# bombclock_1_2.net
KiCad netlist of a schematic drawn in EAGLE
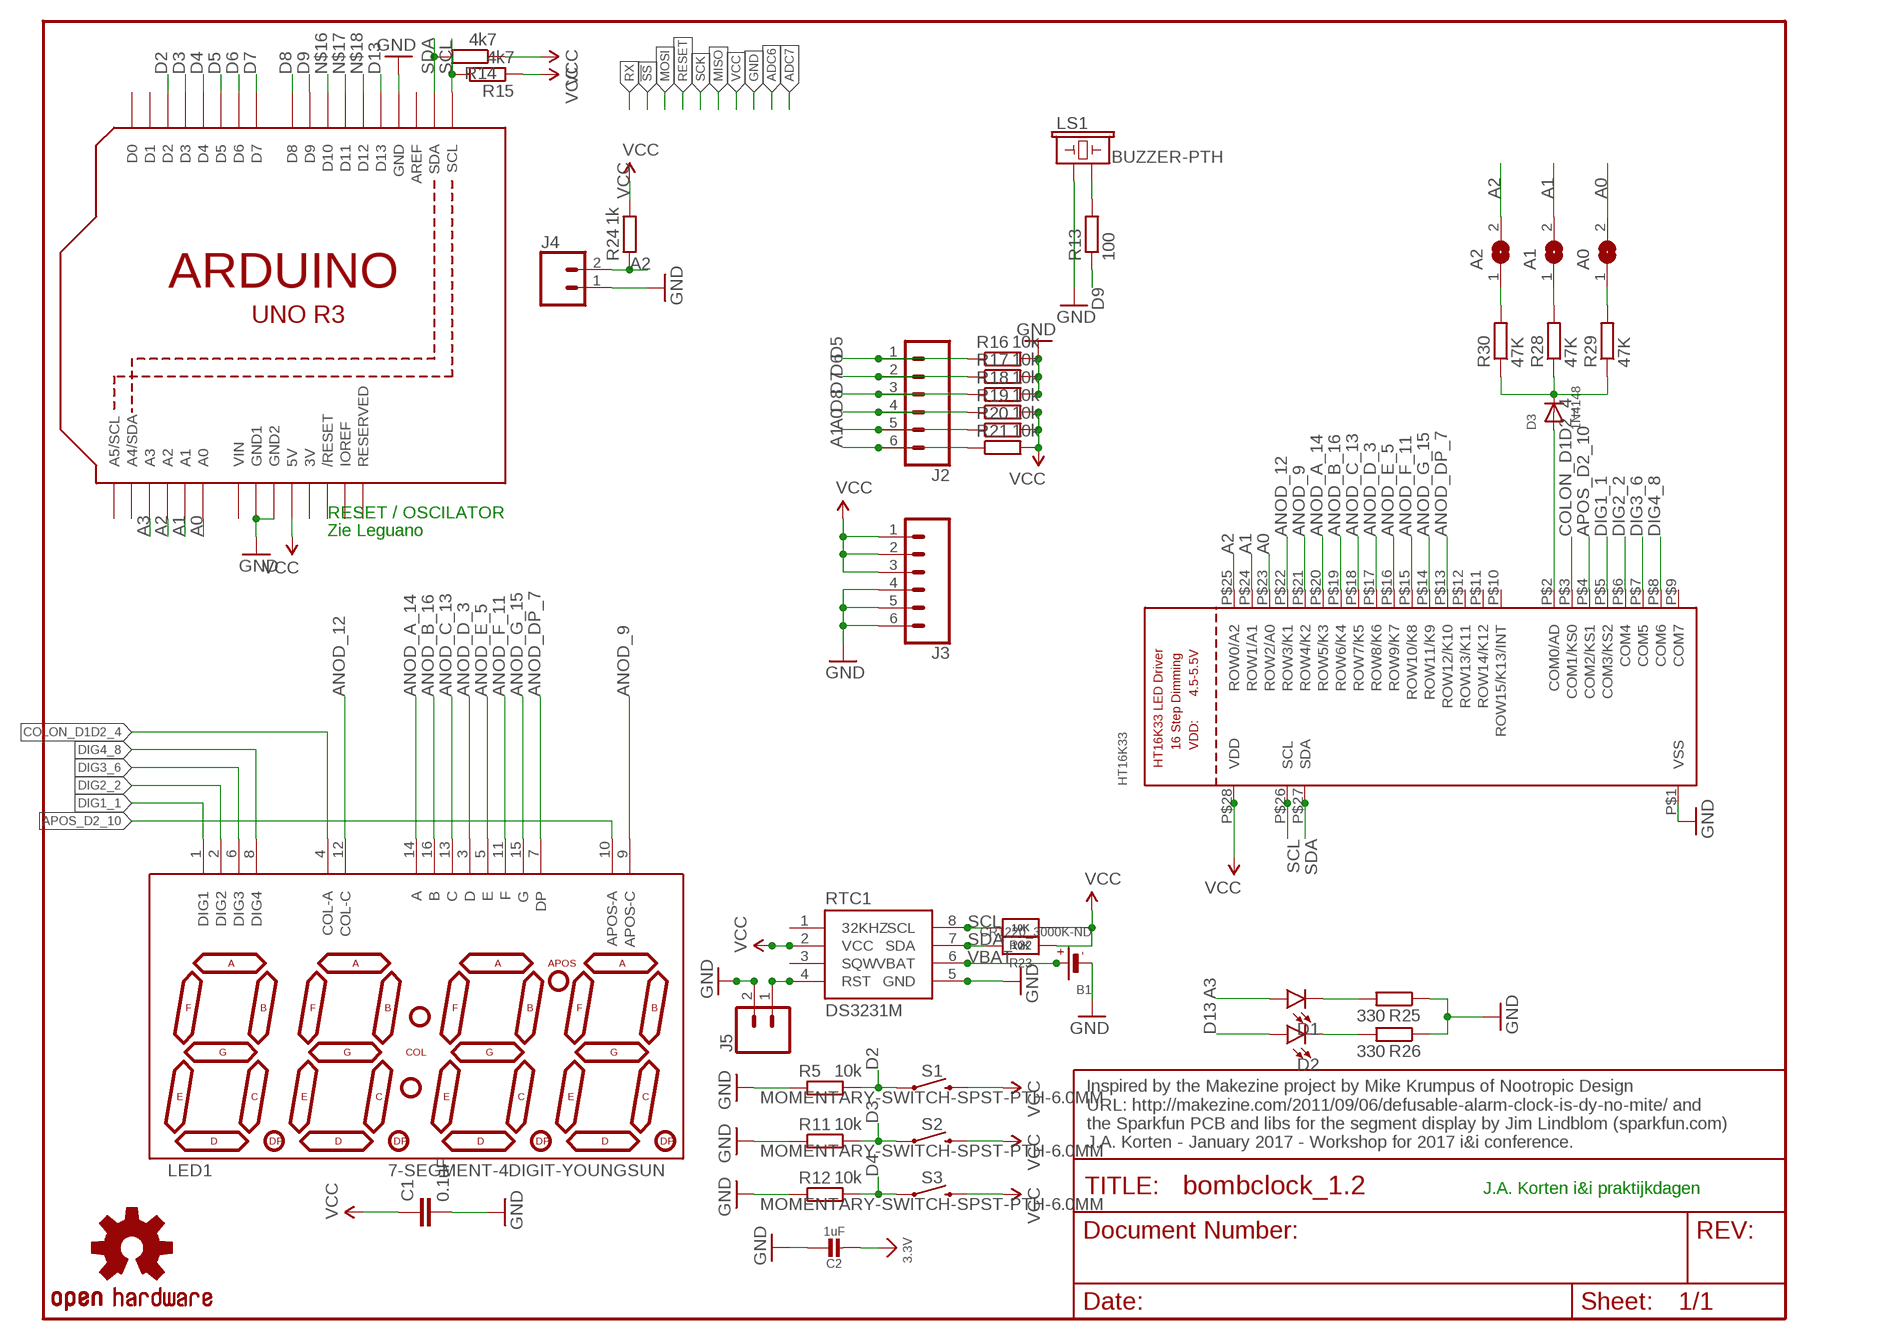
[diagram p0: schematic, sheet 1]

(export (version "E")
  (design (tool "Eeschema 10.0.6"))
  (components
    (comp (ref "A0")
      (value "SOLDERJUMPERREFLOW_NOPASTE")
      (footprint "eagle-import:SOLDERJUMPER_REFLOW_NOPASTE")
      (libsource (lib "eagle-import") (part "SOLDERJUMPERREFLOW_NOPASTE"))
    )
    (comp (ref "A1")
      (value "SOLDERJUMPERREFLOW_NOPASTE")
      (footprint "eagle-import:SOLDERJUMPER_REFLOW_NOPASTE")
      (libsource (lib "eagle-import") (part "SOLDERJUMPERREFLOW_NOPASTE"))
    )
    (comp (ref "A2")
      (value "SOLDERJUMPERREFLOW_NOPASTE")
      (footprint "eagle-import:SOLDERJUMPER_REFLOW_NOPASTE")
      (libsource (lib "eagle-import") (part "SOLDERJUMPERREFLOW_NOPASTE"))
    )
    (comp (ref "B1")
      (value "CR1220_3000K-ND")
      (footprint "eagle-import:CR1220")
      (libsource (lib "eagle-import") (part "BATTERYCR1220_SMT"))
    )
    (comp (ref "C1")
      (value "0.1uF")
      (footprint "eagle-import:0402-CAP")
      (libsource (lib "eagle-import") (part "CAP0402-CAP"))
    )
    (comp (ref "C2")
      (value "1uF")
      (footprint "eagle-import:0805-NO")
      (libsource (lib "eagle-import") (part "CAP_CERAMIC0805-NOOUTLINE"))
    )
    (comp (ref "D1")
      (value "LED5MM")
      (footprint "eagle-import:LED_5MM")
      (libsource (lib "eagle-import") (part "LED5MM"))
    )
    (comp (ref "D2")
      (value "LED5MM")
      (footprint "eagle-import:LED_5MM")
      (libsource (lib "eagle-import") (part "LED5MM"))
    )
    (comp (ref "D3")
      (value "1N4148")
      (footprint "eagle-import:SOD-323F")
      (libsource (lib "eagle-import") (part "DIODESOD-323F"))
    )
    (comp (ref "HT16K33")
      (value "HT16K33_SOP28")
      (footprint "eagle-import:SOP28_300MIL")
      (libsource (lib "eagle-import") (part "HT16K33_SOP28"))
    )
    (comp (ref "J2")
      (value "CONN_06SILK_FEMALE_PTH")
      (footprint "eagle-import:1X06")
      (libsource (lib "eagle-import") (part "CONN_06SILK_FEMALE_PTH"))
    )
    (comp (ref "J3")
      (value "CONN_06SILK_FEMALE_PTH")
      (footprint "eagle-import:1X06")
      (libsource (lib "eagle-import") (part "CONN_06SILK_FEMALE_PTH"))
    )
    (comp (ref "J4")
      (value "CONN_02")
      (footprint "eagle-import:1X02")
      (libsource (lib "eagle-import") (part "CONN_02"))
    )
    (comp (ref "J5")
      (value "CONN_02")
      (footprint "eagle-import:1X02")
      (libsource (lib "eagle-import") (part "CONN_02"))
    )
    (comp (ref "LED1")
      (value "7-SEGMENT-4DIGIT-YOUNGSUN")
      (footprint "eagle-import:7-SEGMENT-4DIGIT-YOUNGSUN")
      (libsource (lib "eagle-import") (part "7-SEGMENT-4DIGIT-YOUNGSUN"))
    )
    (comp (ref "LS1")
      (value "BUZZER-PTH")
      (footprint "eagle-import:BUZZER-12MM")
      (libsource (lib "eagle-import") (part "BUZZER-PTH"))
    )
    (comp (ref "R5")
      (value "10k")
      (footprint "eagle-import:R0603")
      (libsource (lib "eagle-import") (part "R-EU_R0603"))
    )
    (comp (ref "R11")
      (value "10k")
      (footprint "eagle-import:R0603")
      (libsource (lib "eagle-import") (part "R-EU_R0603"))
    )
    (comp (ref "R12")
      (value "10k")
      (footprint "eagle-import:R0603")
      (libsource (lib "eagle-import") (part "R-EU_R0603"))
    )
    (comp (ref "R13")
      (value "100")
      (footprint "eagle-import:R0603")
      (libsource (lib "eagle-import") (part "R-EU_R0603"))
    )
    (comp (ref "R14")
      (value "4k7")
      (footprint "eagle-import:R0603")
      (libsource (lib "eagle-import") (part "R-EU_R0603"))
    )
    (comp (ref "R15")
      (value "4k7")
      (footprint "eagle-import:R0603")
      (libsource (lib "eagle-import") (part "R-EU_R0603"))
    )
    (comp (ref "R16")
      (value "10k")
      (footprint "eagle-import:R0603")
      (libsource (lib "eagle-import") (part "R-EU_R0603"))
    )
    (comp (ref "R17")
      (value "10k")
      (footprint "eagle-import:R0603")
      (libsource (lib "eagle-import") (part "R-EU_R0603"))
    )
    (comp (ref "R18")
      (value "10k")
      (footprint "eagle-import:R0603")
      (libsource (lib "eagle-import") (part "R-EU_R0603"))
    )
    (comp (ref "R19")
      (value "10k")
      (footprint "eagle-import:R0603")
      (libsource (lib "eagle-import") (part "R-EU_R0603"))
    )
    (comp (ref "R20")
      (value "10k")
      (footprint "eagle-import:R0603")
      (libsource (lib "eagle-import") (part "R-EU_R0603"))
    )
    (comp (ref "R21")
      (value "10k")
      (footprint "eagle-import:R0603")
      (libsource (lib "eagle-import") (part "R-EU_R0603"))
    )
    (comp (ref "R22")
      (value "10K")
      (footprint "eagle-import:0805-NO")
      (libsource (lib "eagle-import") (part "RESISTOR0805_NOOUTLINE"))
    )
    (comp (ref "R23")
      (value "10K")
      (footprint "eagle-import:0805-NO")
      (libsource (lib "eagle-import") (part "RESISTOR0805_NOOUTLINE"))
    )
    (comp (ref "R24")
      (value "1k")
      (footprint "eagle-import:R0603")
      (libsource (lib "eagle-import") (part "R-EU_R0603"))
    )
    (comp (ref "R25")
      (value "330")
      (footprint "eagle-import:R0603")
      (libsource (lib "eagle-import") (part "R-EU_R0603"))
    )
    (comp (ref "R26")
      (value "330")
      (footprint "eagle-import:R0603")
      (libsource (lib "eagle-import") (part "R-EU_R0603"))
    )
    (comp (ref "R28")
      (value "47K")
      (footprint "eagle-import:R0603")
      (libsource (lib "eagle-import") (part "resistor_R-EU_R0603"))
    )
    (comp (ref "R29")
      (value "47K")
      (footprint "eagle-import:R0603")
      (libsource (lib "eagle-import") (part "resistor_R-EU_R0603"))
    )
    (comp (ref "R30")
      (value "47K")
      (footprint "eagle-import:R0603")
      (libsource (lib "eagle-import") (part "resistor_R-EU_R0603"))
    )
    (comp (ref "RTC1")
      (value "DS3231M")
      (footprint "eagle-import:SO08")
      (libsource (lib "eagle-import") (part "DS3231M"))
    )
    (comp (ref "S1")
      (value "MOMENTARY-SWITCH-SPST-PTH-6.0MM")
      (footprint "eagle-import:TACTILE_SWITCH_PTH_6.0MM")
      (libsource (lib "eagle-import") (part "MOMENTARY-SWITCH-SPST-PTH-6.0MM"))
    )
    (comp (ref "S2")
      (value "MOMENTARY-SWITCH-SPST-PTH-6.0MM")
      (footprint "eagle-import:TACTILE_SWITCH_PTH_6.0MM")
      (libsource (lib "eagle-import") (part "MOMENTARY-SWITCH-SPST-PTH-6.0MM"))
    )
    (comp (ref "S3")
      (value "MOMENTARY-SWITCH-SPST-PTH-6.0MM")
      (footprint "eagle-import:TACTILE_SWITCH_PTH_6.0MM")
      (libsource (lib "eagle-import") (part "MOMENTARY-SWITCH-SPST-PTH-6.0MM"))
    )
    (comp (ref "U$4")
      (value "OSHW-LOGOS")
      (footprint "eagle-import:OSHW-LOGO-S")
      (libsource (lib "eagle-import") (part "OSHW-LOGOS"))
    )
    (comp (ref "U1")
      (value "ARDUINOR3-DIMENSION")
      (footprint "eagle-import:ARDUINOR3")
      (libsource (lib "eagle-import") (part "ARDUINOR3-DIMENSION"))
    )
  )
  (nets
    (net (code "1") (name "/3V") (class "Default")
      (node (ref "U1") (pin "3V") (pinfunction "3V_3V") (pintype "power_in"))
    )
    (net (code "2") (name "/A0") (class "Default")
      (node (ref "A0") (pin "2") (pinfunction "2_2") (pintype "passive"))
      (node (ref "HT16K33") (pin "P$23") (pinfunction "ROW2/A0_P$23") (pintype "bidirectional"))
      (node (ref "J2") (pin "5") (pinfunction "5_5") (pintype "passive"))
      (node (ref "R20") (pin "1") (pinfunction "1_1") (pintype "passive"))
      (node (ref "U1") (pin "A0") (pinfunction "A0_A0") (pintype "bidirectional"))
    )
    (net (code "3") (name "/A1") (class "Default")
      (node (ref "A1") (pin "2") (pinfunction "2_2") (pintype "passive"))
      (node (ref "HT16K33") (pin "P$24") (pinfunction "ROW1/A1_P$24") (pintype "bidirectional"))
      (node (ref "J2") (pin "6") (pinfunction "6_6") (pintype "passive"))
      (node (ref "R21") (pin "1") (pinfunction "1_1") (pintype "passive"))
      (node (ref "U1") (pin "A1") (pinfunction "A1_A1") (pintype "bidirectional"))
    )
    (net (code "4") (name "/A2") (class "Default")
      (node (ref "A2") (pin "2") (pinfunction "2_2") (pintype "passive"))
      (node (ref "HT16K33") (pin "P$25") (pinfunction "ROW0/A2_P$25") (pintype "bidirectional"))
      (node (ref "J4") (pin "2") (pinfunction "2_2") (pintype "passive"))
      (node (ref "R24") (pin "1") (pinfunction "1_1") (pintype "passive"))
      (node (ref "U1") (pin "A2") (pinfunction "A2_A2") (pintype "bidirectional"))
    )
    (net (code "5") (name "/A3") (class "Default")
      (node (ref "D1") (pin "A") (pinfunction "A_A") (pintype "passive"))
      (node (ref "U1") (pin "A3") (pinfunction "A3_A3") (pintype "bidirectional"))
    )
    (net (code "6") (name "/ANOD_9") (class "Default")
      (node (ref "HT16K33") (pin "P$21") (pinfunction "ROW4/K2_P$21") (pintype "bidirectional"))
      (node (ref "LED1") (pin "9") (pinfunction "APOS-C_9") (pintype "bidirectional"))
    )
    (net (code "7") (name "/ANOD_12") (class "Default")
      (node (ref "HT16K33") (pin "P$22") (pinfunction "ROW3/K1_P$22") (pintype "bidirectional"))
      (node (ref "LED1") (pin "12") (pinfunction "COL-C_12") (pintype "bidirectional"))
    )
    (net (code "8") (name "/ANOD_A_14") (class "Default")
      (node (ref "HT16K33") (pin "P$20") (pinfunction "ROW5/K3_P$20") (pintype "bidirectional"))
      (node (ref "LED1") (pin "14") (pinfunction "A_14") (pintype "bidirectional"))
    )
    (net (code "9") (name "/ANOD_B_16") (class "Default")
      (node (ref "HT16K33") (pin "P$19") (pinfunction "ROW6/K4_P$19") (pintype "bidirectional"))
      (node (ref "LED1") (pin "16") (pinfunction "B_16") (pintype "bidirectional"))
    )
    (net (code "10") (name "/ANOD_C_13") (class "Default")
      (node (ref "HT16K33") (pin "P$18") (pinfunction "ROW7/K5_P$18") (pintype "bidirectional"))
      (node (ref "LED1") (pin "13") (pinfunction "C_13") (pintype "bidirectional"))
    )
    (net (code "11") (name "/ANOD_DP_7") (class "Default")
      (node (ref "HT16K33") (pin "P$13") (pinfunction "ROW12/K10_P$13") (pintype "bidirectional"))
      (node (ref "LED1") (pin "7") (pinfunction "DP_7") (pintype "bidirectional"))
    )
    (net (code "12") (name "/ANOD_D_3") (class "Default")
      (node (ref "HT16K33") (pin "P$17") (pinfunction "ROW8/K6_P$17") (pintype "bidirectional"))
      (node (ref "LED1") (pin "3") (pinfunction "D_3") (pintype "bidirectional"))
    )
    (net (code "13") (name "/ANOD_E_5") (class "Default")
      (node (ref "HT16K33") (pin "P$16") (pinfunction "ROW9/K7_P$16") (pintype "bidirectional"))
      (node (ref "LED1") (pin "5") (pinfunction "E_5") (pintype "bidirectional"))
    )
    (net (code "14") (name "/ANOD_F_11") (class "Default")
      (node (ref "HT16K33") (pin "P$15") (pinfunction "ROW10/K8_P$15") (pintype "bidirectional"))
      (node (ref "LED1") (pin "11") (pinfunction "F_11") (pintype "bidirectional"))
    )
    (net (code "15") (name "/ANOD_G_15") (class "Default")
      (node (ref "HT16K33") (pin "P$14") (pinfunction "ROW11/K9_P$14") (pintype "bidirectional"))
      (node (ref "LED1") (pin "15") (pinfunction "G_15") (pintype "bidirectional"))
    )
    (net (code "16") (name "/D2") (class "Default")
      (node (ref "R5") (pin "2") (pinfunction "2_2") (pintype "passive"))
      (node (ref "S1") (pin "1") (pinfunction "1_1") (pintype "passive"))
      (node (ref "U1") (pin "D2") (pinfunction "D2_D2") (pintype "bidirectional"))
    )
    (net (code "17") (name "/D3") (class "Default")
      (node (ref "R11") (pin "2") (pinfunction "2_2") (pintype "passive"))
      (node (ref "S2") (pin "1") (pinfunction "1_1") (pintype "passive"))
      (node (ref "U1") (pin "D3") (pinfunction "D3_D3") (pintype "bidirectional"))
    )
    (net (code "18") (name "/D4") (class "Default")
      (node (ref "R12") (pin "2") (pinfunction "2_2") (pintype "passive"))
      (node (ref "S3") (pin "1") (pinfunction "1_1") (pintype "passive"))
      (node (ref "U1") (pin "D4") (pinfunction "D4_D4") (pintype "bidirectional"))
    )
    (net (code "19") (name "/D5") (class "Default")
      (node (ref "J2") (pin "1") (pinfunction "1_1") (pintype "passive"))
      (node (ref "R16") (pin "1") (pinfunction "1_1") (pintype "passive"))
      (node (ref "U1") (pin "D5") (pinfunction "D5_D5") (pintype "bidirectional"))
    )
    (net (code "20") (name "/D6") (class "Default")
      (node (ref "J2") (pin "2") (pinfunction "2_2") (pintype "passive"))
      (node (ref "R17") (pin "1") (pinfunction "1_1") (pintype "passive"))
      (node (ref "U1") (pin "D6") (pinfunction "D6_D6") (pintype "bidirectional"))
    )
    (net (code "21") (name "/D7") (class "Default")
      (node (ref "J2") (pin "3") (pinfunction "3_3") (pintype "passive"))
      (node (ref "R18") (pin "1") (pinfunction "1_1") (pintype "passive"))
      (node (ref "U1") (pin "D7") (pinfunction "D7_D7") (pintype "bidirectional"))
    )
    (net (code "22") (name "/D8") (class "Default")
      (node (ref "J2") (pin "4") (pinfunction "4_4") (pintype "passive"))
      (node (ref "R19") (pin "1") (pinfunction "1_1") (pintype "passive"))
      (node (ref "U1") (pin "D8") (pinfunction "D8_D8") (pintype "bidirectional"))
    )
    (net (code "23") (name "/D9") (class "Default")
      (node (ref "R13") (pin "1") (pinfunction "1_1") (pintype "passive"))
      (node (ref "U1") (pin "D9") (pinfunction "D9_D9") (pintype "bidirectional"))
    )
    (net (code "24") (name "/D13") (class "Default")
      (node (ref "D2") (pin "A") (pinfunction "A_A") (pintype "passive"))
      (node (ref "U1") (pin "D13") (pinfunction "D13_D13") (pintype "bidirectional"))
    )
    (net (code "25") (name "/N$16") (class "Default")
      (node (ref "U1") (pin "D10") (pinfunction "D10_D10") (pintype "bidirectional"))
    )
    (net (code "26") (name "/N$17") (class "Default")
      (node (ref "U1") (pin "D11") (pinfunction "D11_D11") (pintype "bidirectional"))
    )
    (net (code "27") (name "/N$18") (class "Default")
      (node (ref "U1") (pin "D12") (pinfunction "D12_D12") (pintype "bidirectional"))
    )
    (net (code "28") (name "/SCL") (class "Default")
      (node (ref "HT16K33") (pin "P$26") (pinfunction "SCL_P$26") (pintype "bidirectional"))
      (node (ref "R15") (pin "2") (pinfunction "2_2") (pintype "passive"))
      (node (ref "R22") (pin "2") (pinfunction "2_2") (pintype "passive"))
      (node (ref "RTC1") (pin "8") (pinfunction "SCL_8") (pintype "bidirectional"))
      (node (ref "U1") (pin "SCL") (pinfunction "SCL_SCL") (pintype "bidirectional"))
    )
    (net (code "29") (name "/SDA") (class "Default")
      (node (ref "HT16K33") (pin "P$27") (pinfunction "SDA_P$27") (pintype "bidirectional"))
      (node (ref "R14") (pin "2") (pinfunction "2_2") (pintype "passive"))
      (node (ref "R23") (pin "2") (pinfunction "2_2") (pintype "passive"))
      (node (ref "RTC1") (pin "7") (pinfunction "SDA_7") (pintype "bidirectional"))
      (node (ref "U1") (pin "SDA") (pinfunction "SDA_SDA") (pintype "bidirectional"))
    )
    (net (code "30") (name "/VBAT") (class "Default")
      (node (ref "B1") (pin "+$1") (pinfunction "+_+$1") (pintype "passive"))
      (node (ref "RTC1") (pin "6") (pinfunction "VBAT_6") (pintype "power_in"))
    )
    (net (code "31") (name "/VIN") (class "Default")
      (node (ref "U1") (pin "VIN") (pinfunction "VIN_VIN") (pintype "power_in"))
    )
    (net (code "33") (name "3.3V") (class "Default")
      (node (ref "C2") (pin "2") (pinfunction "2_2") (pintype "passive"))
    )
    (net (code "36") (name "APOS_D2_10") (class "Default")
      (node (ref "HT16K33") (pin "P$4") (pinfunction "COM2/KS1_P$4") (pintype "bidirectional"))
      (node (ref "LED1") (pin "10") (pinfunction "APOS-A_10") (pintype "bidirectional"))
    )
    (net (code "37") (name "COLON_D1D2_4") (class "Default")
      (node (ref "HT16K33") (pin "P$3") (pinfunction "COM1/KS0_P$3") (pintype "bidirectional"))
      (node (ref "LED1") (pin "4") (pinfunction "COL-A_4") (pintype "bidirectional"))
    )
    (net (code "38") (name "DIG1_1") (class "Default")
      (node (ref "HT16K33") (pin "P$5") (pinfunction "COM3/KS2_P$5") (pintype "bidirectional"))
      (node (ref "LED1") (pin "1") (pinfunction "DIG1_1") (pintype "bidirectional"))
    )
    (net (code "39") (name "DIG2_2") (class "Default")
      (node (ref "HT16K33") (pin "P$6") (pinfunction "COM4_P$6") (pintype "bidirectional"))
      (node (ref "LED1") (pin "2") (pinfunction "DIG2_2") (pintype "bidirectional"))
    )
    (net (code "40") (name "DIG3_6") (class "Default")
      (node (ref "HT16K33") (pin "P$7") (pinfunction "COM5_P$7") (pintype "bidirectional"))
      (node (ref "LED1") (pin "6") (pinfunction "DIG3_6") (pintype "bidirectional"))
    )
    (net (code "41") (name "DIG4_8") (class "Default")
      (node (ref "HT16K33") (pin "P$8") (pinfunction "COM6_P$8") (pintype "bidirectional"))
      (node (ref "LED1") (pin "8") (pinfunction "DIG4_8") (pintype "bidirectional"))
    )
    (net (code "42") (name "GND") (class "Default")
      (node (ref "B1") (pin "-") (pinfunction "-_-") (pintype "passive"))
      (node (ref "C1") (pin "2") (pinfunction "2_2") (pintype "passive"))
      (node (ref "C2") (pin "1") (pinfunction "1_1") (pintype "passive"))
      (node (ref "HT16K33") (pin "P$1") (pinfunction "VSS_P$1") (pintype "bidirectional"))
      (node (ref "J3") (pin "4") (pinfunction "4_4") (pintype "passive"))
      (node (ref "J3") (pin "5") (pinfunction "5_5") (pintype "passive"))
      (node (ref "J3") (pin "6") (pinfunction "6_6") (pintype "passive"))
      (node (ref "J4") (pin "1") (pinfunction "1_1") (pintype "passive"))
      (node (ref "J5") (pin "2") (pinfunction "2_2") (pintype "passive"))
      (node (ref "LS1") (pin "+") (pinfunction "1_+") (pintype "passive"))
      (node (ref "R11") (pin "1") (pinfunction "1_1") (pintype "passive"))
      (node (ref "R12") (pin "1") (pinfunction "1_1") (pintype "passive"))
      (node (ref "R16") (pin "2") (pinfunction "2_2") (pintype "passive"))
      (node (ref "R17") (pin "2") (pinfunction "2_2") (pintype "passive"))
      (node (ref "R18") (pin "2") (pinfunction "2_2") (pintype "passive"))
      (node (ref "R25") (pin "1") (pinfunction "1_1") (pintype "passive"))
      (node (ref "R26") (pin "1") (pinfunction "1_1") (pintype "passive"))
      (node (ref "R5") (pin "1") (pinfunction "1_1") (pintype "passive"))
      (node (ref "RTC1") (pin "5") (pinfunction "GND_5") (pintype "power_in"))
      (node (ref "U1") (pin "GND") (pinfunction "GND_GND") (pintype "power_in"))
      (node (ref "U1") (pin "GND1") (pinfunction "GND1_GND1") (pintype "power_in"))
      (node (ref "U1") (pin "GND2") (pinfunction "GND2_GND2") (pintype "power_in"))
    )
    (net (code "45") (name "Net-(A0-Pad1)") (class "Default")
      (node (ref "A0") (pin "1") (pinfunction "1_1") (pintype "passive"))
      (node (ref "R29") (pin "2") (pinfunction "2_2") (pintype "passive"))
    )
    (net (code "46") (name "Net-(A1-Pad1)") (class "Default")
      (node (ref "A1") (pin "1") (pinfunction "1_1") (pintype "passive"))
      (node (ref "R28") (pin "2") (pinfunction "2_2") (pintype "passive"))
    )
    (net (code "47") (name "Net-(A2-Pad1)") (class "Default")
      (node (ref "A2") (pin "1") (pinfunction "1_1") (pintype "passive"))
      (node (ref "R30") (pin "2") (pinfunction "2_2") (pintype "passive"))
    )
    (net (code "48") (name "Net-(D1-C)") (class "Default")
      (node (ref "D1") (pin "K") (pinfunction "C_K") (pintype "passive"))
      (node (ref "R25") (pin "2") (pinfunction "2_2") (pintype "passive"))
    )
    (net (code "49") (name "Net-(D2-C)") (class "Default")
      (node (ref "D2") (pin "K") (pinfunction "C_K") (pintype "passive"))
      (node (ref "R26") (pin "2") (pinfunction "2_2") (pintype "passive"))
    )
    (net (code "50") (name "Net-(D3-PadC)") (class "Default")
      (node (ref "D3") (pin "C") (pinfunction "C_C") (pintype "passive"))
      (node (ref "R28") (pin "1") (pinfunction "1_1") (pintype "passive"))
      (node (ref "R29") (pin "1") (pinfunction "1_1") (pintype "passive"))
      (node (ref "R30") (pin "1") (pinfunction "1_1") (pintype "passive"))
    )
    (net (code "51") (name "Net-(HT16K33-COM0{slash}AD)") (class "Default")
      (node (ref "D3") (pin "A") (pinfunction "A_A") (pintype "passive"))
      (node (ref "HT16K33") (pin "P$2") (pinfunction "COM0/AD_P$2") (pintype "bidirectional"))
    )
    (net (code "52") (name "Net-(LS1-2)") (class "Default")
      (node (ref "LS1") (pin "-") (pinfunction "2_-") (pintype "passive"))
      (node (ref "R13") (pin "2") (pinfunction "2_2") (pintype "passive"))
    )
    (net (code "53") (name "Net-(RTC1-RST)") (class "Default")
      (node (ref "J5") (pin "1") (pinfunction "1_1") (pintype "passive"))
      (node (ref "RTC1") (pin "4") (pinfunction "RST_4") (pintype "bidirectional"))
    )
    (net (code "57") (name "VCC") (class "Default")
      (node (ref "C1") (pin "1") (pinfunction "1_1") (pintype "passive"))
      (node (ref "HT16K33") (pin "P$28") (pinfunction "VDD_P$28") (pintype "bidirectional"))
      (node (ref "J3") (pin "1") (pinfunction "1_1") (pintype "passive"))
      (node (ref "J3") (pin "2") (pinfunction "2_2") (pintype "passive"))
      (node (ref "J3") (pin "3") (pinfunction "3_3") (pintype "passive"))
      (node (ref "R14") (pin "1") (pinfunction "1_1") (pintype "passive"))
      (node (ref "R15") (pin "1") (pinfunction "1_1") (pintype "passive"))
      (node (ref "R19") (pin "2") (pinfunction "2_2") (pintype "passive"))
      (node (ref "R20") (pin "2") (pinfunction "2_2") (pintype "passive"))
      (node (ref "R21") (pin "2") (pinfunction "2_2") (pintype "passive"))
      (node (ref "R22") (pin "1") (pinfunction "1_1") (pintype "passive"))
      (node (ref "R23") (pin "1") (pinfunction "1_1") (pintype "passive"))
      (node (ref "R24") (pin "2") (pinfunction "2_2") (pintype "passive"))
      (node (ref "RTC1") (pin "2") (pinfunction "VCC_2") (pintype "power_in"))
      (node (ref "S1") (pin "3") (pinfunction "2_3") (pintype "passive"))
      (node (ref "S2") (pin "3") (pinfunction "2_3") (pintype "passive"))
      (node (ref "S3") (pin "3") (pinfunction "2_3") (pintype "passive"))
      (node (ref "U1") (pin "5V") (pinfunction "5V_5V") (pintype "power_in"))
    )
    (net (code "58") (name "unconnected-(HT16K33-COM7-PadP$9)") (class "Default")
      (node (ref "HT16K33") (pin "P$9") (pinfunction "COM7_P$9") (pintype "bidirectional"))
    )
    (net (code "59") (name "unconnected-(HT16K33-ROW13{slash}K11-PadP$12)") (class "Default")
      (node (ref "HT16K33") (pin "P$12") (pinfunction "ROW13/K11_P$12") (pintype "bidirectional"))
    )
    (net (code "60") (name "unconnected-(HT16K33-ROW14{slash}K12-PadP$11)") (class "Default")
      (node (ref "HT16K33") (pin "P$11") (pinfunction "ROW14/K12_P$11") (pintype "bidirectional"))
    )
    (net (code "61") (name "unconnected-(HT16K33-ROW15{slash}K13{slash}INT-PadP$10)") (class "Default")
      (node (ref "HT16K33") (pin "P$10") (pinfunction "ROW15/K13/INT_P$10") (pintype "bidirectional"))
    )
    (net (code "62") (name "unconnected-(RTC1-32KHZ-Pad1)") (class "Default")
      (node (ref "RTC1") (pin "1") (pinfunction "32KHZ_1") (pintype "output"))
    )
    (net (code "63") (name "unconnected-(RTC1-SQW-Pad3)") (class "Default")
      (node (ref "RTC1") (pin "3") (pinfunction "SQW_3") (pintype "output"))
    )
    (net (code "64") (name "unconnected-(U1-A4{slash}SDA-PadA4)") (class "Default")
      (node (ref "U1") (pin "A4") (pinfunction "A4/SDA_A4") (pintype "bidirectional"))
    )
    (net (code "65") (name "unconnected-(U1-A5{slash}SCL-PadA5)") (class "Default")
      (node (ref "U1") (pin "A5") (pinfunction "A5/SCL_A5") (pintype "bidirectional"))
    )
    (net (code "66") (name "unconnected-(U1-PadAREF)") (class "Default")
      (node (ref "U1") (pin "AREF") (pinfunction "AREF_AREF") (pintype "bidirectional"))
    )
    (net (code "67") (name "unconnected-(U1-PadD0)") (class "Default")
      (node (ref "U1") (pin "D0") (pinfunction "D0_D0") (pintype "bidirectional"))
    )
    (net (code "68") (name "unconnected-(U1-PadD1)") (class "Default")
      (node (ref "U1") (pin "D1") (pinfunction "D1_D1") (pintype "bidirectional"))
    )
    (net (code "69") (name "unconnected-(U1-PadIOREF)") (class "Default")
      (node (ref "U1") (pin "IOREF") (pinfunction "IOREF_IOREF") (pintype "output"))
    )
    (net (code "70") (name "unconnected-(U1-PadRESERVED)") (class "Default")
      (node (ref "U1") (pin "RESERVED") (pinfunction "RESERVED_RESERVED") (pintype "no_connect"))
    )
    (net (code "71") (name "unconnected-(U1-{slash}RESET-PadRESET)") (class "Default")
      (node (ref "U1") (pin "RESET") (pinfunction "/RESET_RESET") (pintype "bidirectional"))
    )
  )
)
